# JTAG.net
KiCad netlist of a schematic drawn in Altium Designer
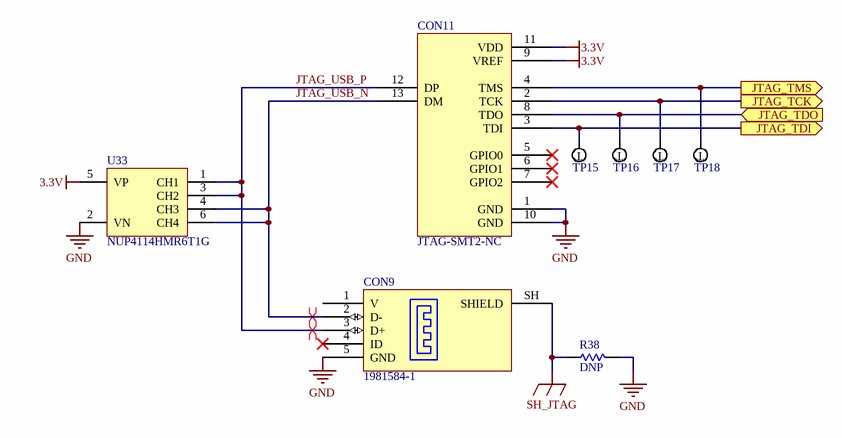
[diagram p0: JTAG.SchDoc]

(export (version "E")
  (design (tool "Eeschema 10.0.6"))
  (components
    (comp (ref "CON9")
      (value "1981584-1")
      (footprint "1981584-1")
      (description "CONN RCPT MICRO USB TYPE AB")
      (libsource (lib "AMDC") (part "1981584-1"))
    )
    (comp (ref "CON11")
      (value "JTAG-SMT2-NC")
      (footprint "JTAG-SMT2-NC")
      (description "MOD PROGRAMMING JTAG-SMT2-NC")
      (libsource (lib "AMDC") (part "JTAG-SMT2-NC"))
    )
    (comp (ref "R38")
      (value "DNP")
      (footprint "0603-RES")
      (description "Resistor")
      (libsource (lib "AMDC") (part "Resistor"))
    )
    (comp (ref "TP15") (value "Test Point") (footprint "TP-125") (libsource (lib "AMDC") (part "Test Point")))
    (comp (ref "TP16") (value "Test Point") (footprint "TP-125") (libsource (lib "AMDC") (part "Test Point")))
    (comp (ref "TP17") (value "Test Point") (footprint "TP-125") (libsource (lib "AMDC") (part "Test Point")))
    (comp (ref "TP18") (value "Test Point") (footprint "TP-125") (libsource (lib "AMDC") (part "Test Point")))
    (comp (ref "U33")
      (value "NUP4114HMR6T1G")
      (footprint "TSOP95P280X110-6N")
      (description "TVS DIODE 5.5V 10V 6TSOP")
      (libsource (lib "AMDC") (part "NUP4114HMR6T1G"))
    )
  )
  (nets
    (net (code "1") (name "/JTAG_TCK") (class "Default")
      (node (ref "CON11") (pin "2") (pinfunction "TCK_2") (pintype "passive"))
      (node (ref "TP17") (pin "1") (pinfunction "1_1") (pintype "passive"))
    )
    (net (code "2") (name "/JTAG_TDI") (class "Default")
      (node (ref "CON11") (pin "3") (pinfunction "TDI_3") (pintype "passive"))
      (node (ref "TP15") (pin "1") (pinfunction "1_1") (pintype "passive"))
    )
    (net (code "3") (name "/JTAG_TDO") (class "Default")
      (node (ref "CON11") (pin "8") (pinfunction "TDO_8") (pintype "passive"))
      (node (ref "TP16") (pin "1") (pinfunction "1_1") (pintype "passive"))
    )
    (net (code "4") (name "/JTAG_TMS") (class "Default")
      (node (ref "CON11") (pin "4") (pinfunction "TMS_4") (pintype "passive"))
      (node (ref "TP18") (pin "1") (pinfunction "1_1") (pintype "passive"))
    )
    (net (code "5") (name "/JTAG_USB_N") (class "Default")
      (node (ref "CON11") (pin "13") (pinfunction "DM_13") (pintype "passive"))
      (node (ref "CON9") (pin "2") (pinfunction "D-_2") (pintype "bidirectional"))
      (node (ref "U33") (pin "4") (pinfunction "CH3_4") (pintype "passive"))
      (node (ref "U33") (pin "6") (pinfunction "CH4_6") (pintype "passive"))
    )
    (net (code "6") (name "/JTAG_USB_P") (class "Default")
      (node (ref "CON11") (pin "12") (pinfunction "DP_12") (pintype "passive"))
      (node (ref "CON9") (pin "3") (pinfunction "D+_3") (pintype "bidirectional"))
      (node (ref "U33") (pin "1") (pinfunction "CH1_1") (pintype "passive"))
      (node (ref "U33") (pin "3") (pinfunction "CH2_3") (pintype "passive"))
    )
    (net (code "7") (name "3.3V") (class "Default")
      (node (ref "CON11") (pin "11") (pinfunction "VDD_11") (pintype "passive"))
      (node (ref "CON11") (pin "9") (pinfunction "VREF_9") (pintype "passive"))
      (node (ref "U33") (pin "5") (pinfunction "VP_5") (pintype "passive"))
    )
    (net (code "8") (name "GND") (class "Default")
      (node (ref "CON11") (pin "1") (pinfunction "GND_1") (pintype "passive"))
      (node (ref "CON11") (pin "10") (pinfunction "GND_10") (pintype "passive"))
      (node (ref "CON9") (pin "5") (pinfunction "GND_5") (pintype "passive"))
      (node (ref "R38") (pin "2") (pinfunction "2_2") (pintype "passive"))
      (node (ref "U33") (pin "2") (pinfunction "VN_2") (pintype "passive"))
    )
    (net (code "9") (name "SH_JTAG") (class "Default")
      (node (ref "CON9") (pin "SH") (pinfunction "SHIELD_SH") (pintype "passive"))
      (node (ref "R38") (pin "1") (pinfunction "1_1") (pintype "passive"))
    )
    (net (code "10") (name "unconnected-(CON9-ID-Pad4)") (class "Default")
      (node (ref "CON9") (pin "4") (pinfunction "ID_4") (pintype "passive+no_connect"))
    )
    (net (code "11") (name "unconnected-(CON9-V-Pad1)") (class "Default")
      (node (ref "CON9") (pin "1") (pinfunction "V_1") (pintype "passive"))
    )
    (net (code "12") (name "unconnected-(CON11-GPIO0-Pad5)") (class "Default")
      (node (ref "CON11") (pin "5") (pinfunction "GPIO0_5") (pintype "passive+no_connect"))
    )
    (net (code "13") (name "unconnected-(CON11-GPIO1-Pad6)") (class "Default")
      (node (ref "CON11") (pin "6") (pinfunction "GPIO1_6") (pintype "passive+no_connect"))
    )
    (net (code "14") (name "unconnected-(CON11-GPIO2-Pad7)") (class "Default")
      (node (ref "CON11") (pin "7") (pinfunction "GPIO2_7") (pintype "passive+no_connect"))
    )
  )
)
